# usbpropicprog-v2.net
KiCad netlist of a schematic drawn in EAGLE
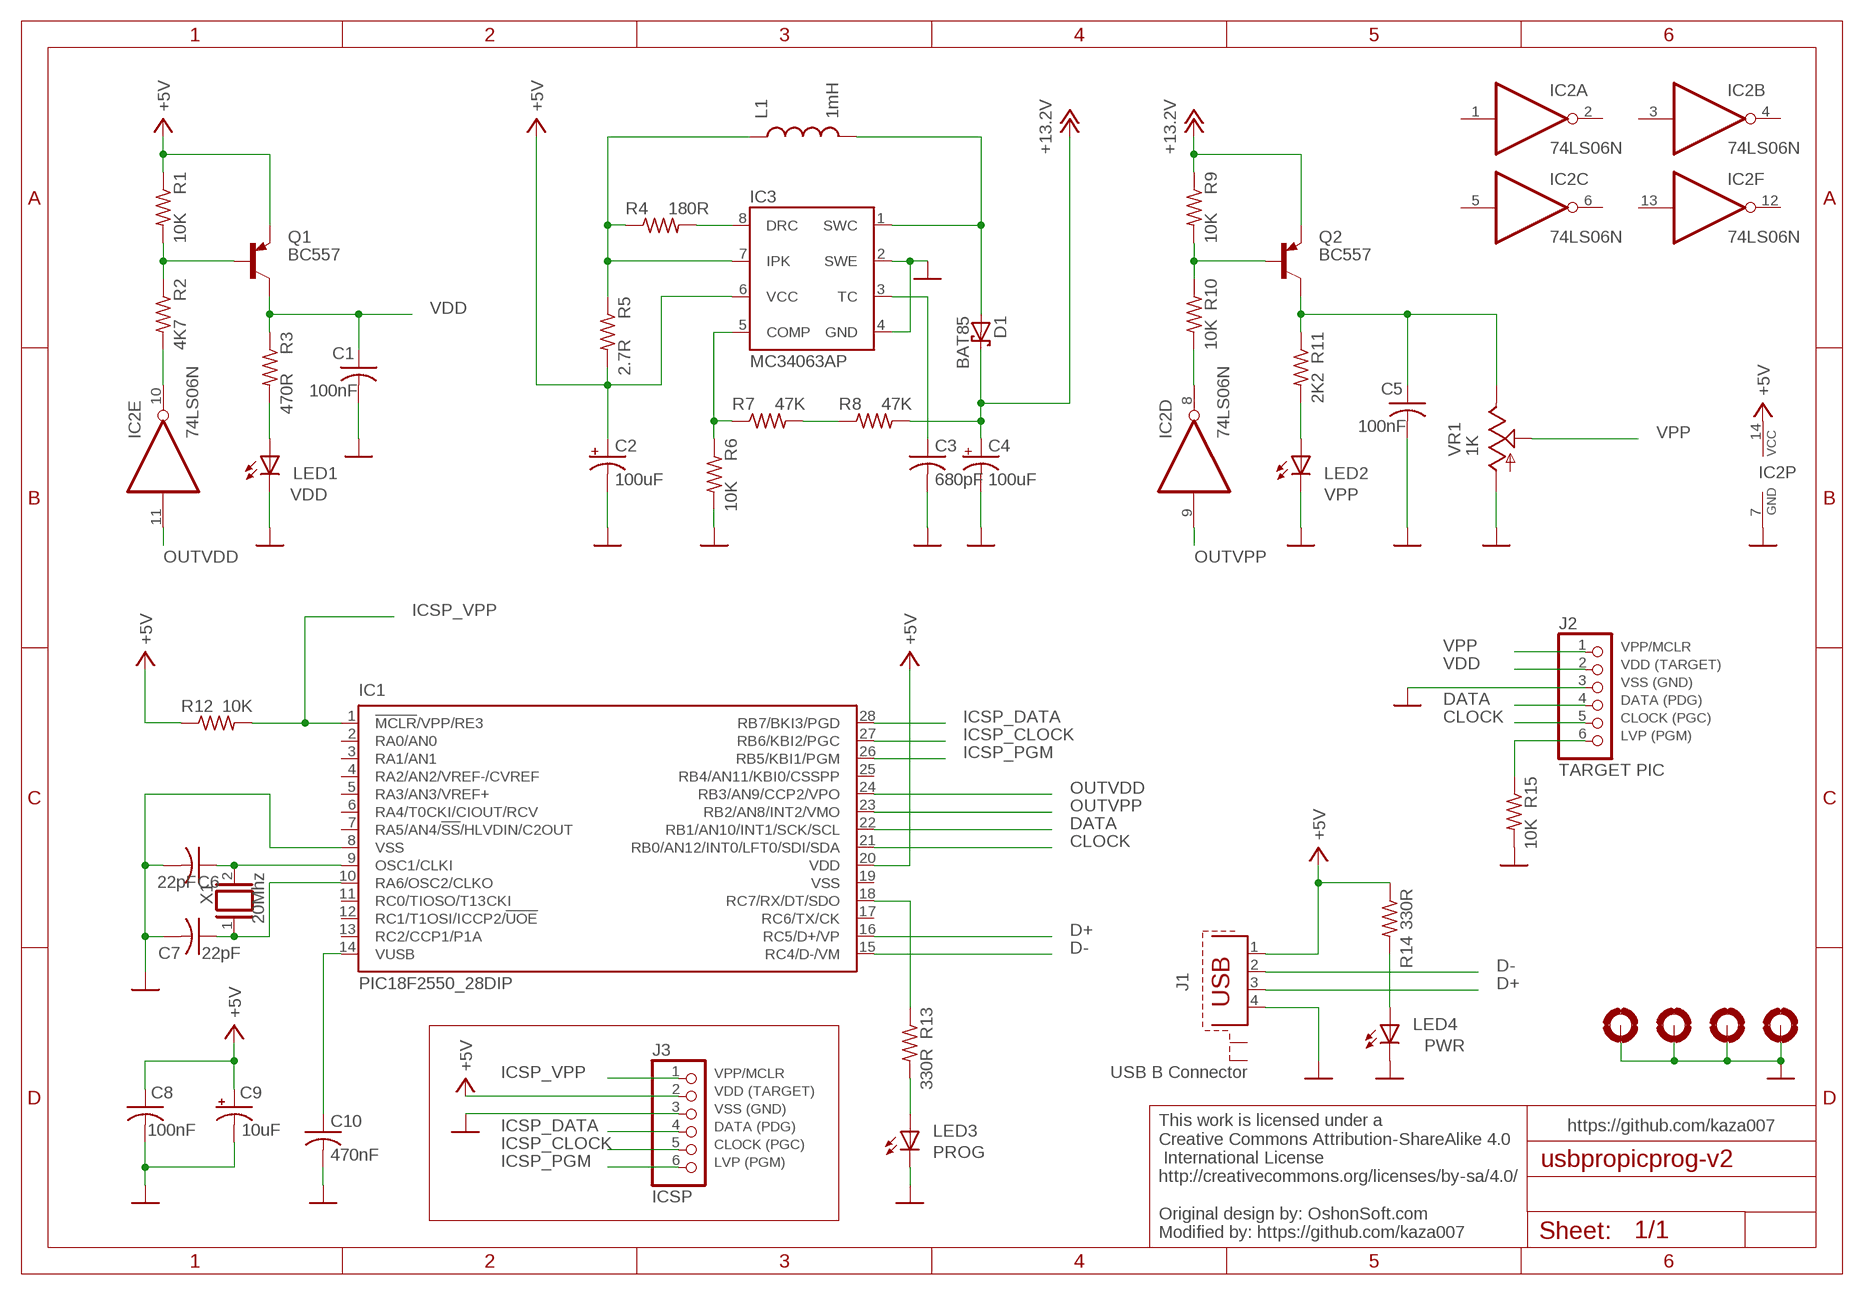
[diagram p0: schematic, sheet 1]

(export (version "E")
  (design (tool "Eeschema 10.0.6"))
  (components
    (comp (ref "C1")
      (value "100nF")
      (footprint "eagle-import:C050-025X075")
      (libsource (lib "eagle-import") (part "C-US050-025X075"))
    )
    (comp (ref "C2")
      (value "100uF")
      (footprint "eagle-import:E2,5-6,3")
      (libsource (lib "eagle-import") (part "POL-CAP-USE2,5-6,3"))
    )
    (comp (ref "C3")
      (value "680pF")
      (footprint "eagle-import:C050-025X075")
      (libsource (lib "eagle-import") (part "C-US050-025X075"))
    )
    (comp (ref "C4")
      (value "100uF")
      (footprint "eagle-import:E2,5-6,3")
      (libsource (lib "eagle-import") (part "POL-CAP-USE2,5-6,3"))
    )
    (comp (ref "C5")
      (value "100nF")
      (footprint "eagle-import:C050-025X075")
      (libsource (lib "eagle-import") (part "C-US050-025X075"))
    )
    (comp (ref "C6")
      (value "22pF")
      (footprint "eagle-import:C025-024X044")
      (libsource (lib "eagle-import") (part "C-US025-024X044"))
    )
    (comp (ref "C7")
      (value "22pF")
      (footprint "eagle-import:C025-024X044")
      (libsource (lib "eagle-import") (part "C-US025-024X044"))
    )
    (comp (ref "C8")
      (value "100nF")
      (footprint "eagle-import:C050-025X075")
      (libsource (lib "eagle-import") (part "C-US050-025X075"))
    )
    (comp (ref "C9")
      (value "10uF")
      (footprint "eagle-import:E2-5")
      (libsource (lib "eagle-import") (part "CPOL-USE2-5"))
    )
    (comp (ref "C10")
      (value "470nF")
      (footprint "eagle-import:C050-035X075")
      (libsource (lib "eagle-import") (part "C-US050-035X075"))
    )
    (comp (ref "D1")
      (value "BAT85")
      (footprint "eagle-import:DO41-7.6")
      (libsource (lib "eagle-import") (part "1N5819-T"))
    )
    (comp (ref "H1")
      (value "MOUNT-PAD-ROUND2.8")
      (footprint "eagle-import:2,8-PAD")
      (libsource (lib "eagle-import") (part "MOUNT-PAD-ROUND2.8"))
    )
    (comp (ref "H2")
      (value "MOUNT-PAD-ROUND2.8")
      (footprint "eagle-import:2,8-PAD")
      (libsource (lib "eagle-import") (part "MOUNT-PAD-ROUND2.8"))
    )
    (comp (ref "H3")
      (value "MOUNT-PAD-ROUND2.8")
      (footprint "eagle-import:2,8-PAD")
      (libsource (lib "eagle-import") (part "MOUNT-PAD-ROUND2.8"))
    )
    (comp (ref "H4")
      (value "MOUNT-PAD-ROUND2.8")
      (footprint "eagle-import:2,8-PAD")
      (libsource (lib "eagle-import") (part "MOUNT-PAD-ROUND2.8"))
    )
    (comp (ref "IC1")
      (value "PIC18F2550_28DIP")
      (footprint "eagle-import:DIL28-3")
      (fields (field (name "MF") "MICROCHIP") (field (name "MPN") "PIC18F2550-I/SP"))
      (libsource (lib "eagle-import") (part "PIC18F2_28DIP550"))
    )
    (comp (ref "IC2")
      (value "74LS06N")
      (footprint "eagle-import:DIL14")
      (libsource (lib "eagle-import") (part "7406NLS"))
    )
    (comp (ref "IC3")
      (value "MC34063AP")
      (footprint "eagle-import:DIL-08")
      (libsource (lib "eagle-import") (part "MC34063AP"))
    )
    (comp (ref "J1")
      (value "USB B Connector")
      (footprint "eagle-import:PN61729-S")
      (libsource (lib "eagle-import") (part "PN61729-S"))
    )
    (comp (ref "J2")
      (value "TARGET PIC")
      (footprint "eagle-import:1X06")
      (libsource (lib "eagle-import") (part "PINHD-1X6"))
    )
    (comp (ref "J3")
      (value "ICSP")
      (footprint "eagle-import:1X06")
      (libsource (lib "eagle-import") (part "PINHD-1X6"))
    )
    (comp (ref "L1")
      (value "1mH")
      (footprint "eagle-import:RLB0912")
      (libsource (lib "eagle-import") (part "INDUCTORRLB0912"))
    )
    (comp (ref "LED1")
      (value "VDD")
      (footprint "eagle-import:LED5MM")
      (libsource (lib "eagle-import") (part "LED5MM"))
    )
    (comp (ref "LED2")
      (value "VPP")
      (footprint "eagle-import:LED5MM")
      (libsource (lib "eagle-import") (part "LED5MM"))
    )
    (comp (ref "LED3")
      (value "PROG")
      (footprint "eagle-import:LED5MM")
      (libsource (lib "eagle-import") (part "LED5MM"))
    )
    (comp (ref "LED4")
      (value "PWR")
      (footprint "eagle-import:LED5MM")
      (libsource (lib "eagle-import") (part "LED5MM"))
    )
    (comp (ref "Q1")
      (value "BC557")
      (footprint "eagle-import:TO92-EBC")
      (libsource (lib "eagle-import") (part "BC557"))
    )
    (comp (ref "Q2")
      (value "BC557")
      (footprint "eagle-import:TO92-EBC")
      (libsource (lib "eagle-import") (part "BC557"))
    )
    (comp (ref "R1")
      (value "10K")
      (footprint "eagle-import:0207_10")
      (libsource (lib "eagle-import") (part "R-US_0207/10"))
    )
    (comp (ref "R2")
      (value "4K7")
      (footprint "eagle-import:0207_10")
      (libsource (lib "eagle-import") (part "R-US_0207/10"))
    )
    (comp (ref "R3")
      (value "470R")
      (footprint "eagle-import:0207_10")
      (libsource (lib "eagle-import") (part "R-US_0207/10"))
    )
    (comp (ref "R4")
      (value "180R")
      (footprint "eagle-import:0207_10")
      (libsource (lib "eagle-import") (part "R-US_0207/10"))
    )
    (comp (ref "R5")
      (value "2.7R")
      (footprint "eagle-import:0207_10")
      (libsource (lib "eagle-import") (part "R-US_0207/10"))
    )
    (comp (ref "R6")
      (value "10K")
      (footprint "eagle-import:0207_10")
      (libsource (lib "eagle-import") (part "R-US_0207/10"))
    )
    (comp (ref "R7")
      (value "47K")
      (footprint "eagle-import:0207_10")
      (libsource (lib "eagle-import") (part "R-US_0207/10"))
    )
    (comp (ref "R8")
      (value "47K")
      (footprint "eagle-import:0207_10")
      (libsource (lib "eagle-import") (part "R-US_0207/10"))
    )
    (comp (ref "R9")
      (value "10K")
      (footprint "eagle-import:0207_10")
      (libsource (lib "eagle-import") (part "R-US_0207/10"))
    )
    (comp (ref "R10")
      (value "10K")
      (footprint "eagle-import:0207_10")
      (libsource (lib "eagle-import") (part "R-US_0207/10"))
    )
    (comp (ref "R11")
      (value "2K2")
      (footprint "eagle-import:0207_10")
      (libsource (lib "eagle-import") (part "R-US_0207/10"))
    )
    (comp (ref "R12")
      (value "10K")
      (footprint "eagle-import:0207_10")
      (libsource (lib "eagle-import") (part "R-US_0207/10"))
    )
    (comp (ref "R13")
      (value "330R")
      (footprint "eagle-import:0207_10")
      (libsource (lib "eagle-import") (part "R-US_0207/10"))
    )
    (comp (ref "R14")
      (value "330R")
      (footprint "eagle-import:0207_10")
      (libsource (lib "eagle-import") (part "R-US_0207/10"))
    )
    (comp (ref "R15")
      (value "10K")
      (footprint "eagle-import:0207_10")
      (libsource (lib "eagle-import") (part "R-US_0207/10"))
    )
    (comp (ref "VR1")
      (value "1K")
      (footprint "eagle-import:R-TRIMMT93YA")
      (libsource (lib "eagle-import") (part "R-TRIMM_US"))
    )
    (comp (ref "X1")
      (value "20Mhz")
      (footprint "eagle-import:QS")
      (libsource (lib "eagle-import") (part "XTAL/S"))
    )
  )
  (nets
    (net (code "1") (name "+5V") (class "Default")
      (node (ref "C2") (pin "+") (pinfunction "+_+") (pintype "passive"))
      (node (ref "C8") (pin "1") (pinfunction "1_1") (pintype "passive"))
      (node (ref "C9") (pin "+") (pinfunction "+_+") (pintype "passive"))
      (node (ref "IC1") (pin "20") (pinfunction "VDD_20") (pintype "power_in"))
      (node (ref "IC2") (pin "14") (pinfunction "VCC_14") (pintype "power_in"))
      (node (ref "IC3") (pin "6") (pinfunction "VCC_6") (pintype "power_in"))
      (node (ref "J1") (pin "1") (pinfunction "1_1") (pintype "passive"))
      (node (ref "J3") (pin "2") (pinfunction "2_2") (pintype "passive"))
      (node (ref "Q1") (pin "E") (pinfunction "E_E") (pintype "passive"))
      (node (ref "R1") (pin "1") (pinfunction "1_1") (pintype "passive"))
      (node (ref "R12") (pin "1") (pinfunction "1_1") (pintype "passive"))
      (node (ref "R14") (pin "1") (pinfunction "1_1") (pintype "passive"))
      (node (ref "R5") (pin "2") (pinfunction "2_2") (pintype "passive"))
    )
    (net (code "2") (name "+13.2V") (class "Default")
      (node (ref "C4") (pin "+") (pinfunction "+_+") (pintype "passive"))
      (node (ref "D1") (pin "C") (pinfunction "C_C") (pintype "passive"))
      (node (ref "Q2") (pin "E") (pinfunction "E_E") (pintype "passive"))
      (node (ref "R8") (pin "2") (pinfunction "2_2") (pintype "passive"))
      (node (ref "R9") (pin "1") (pinfunction "1_1") (pintype "passive"))
    )
    (net (code "3") (name "/CLOCK") (class "Default")
      (node (ref "IC1") (pin "21") (pinfunction "RB0/AN12/INT0/LFT0/SDI/SDA_21") (pintype "bidirectional"))
      (node (ref "J2") (pin "5") (pinfunction "5_5") (pintype "passive"))
    )
    (net (code "4") (name "/D+") (class "Default")
      (node (ref "IC1") (pin "16") (pinfunction "RC5/D+/VP_16") (pintype "bidirectional"))
      (node (ref "J1") (pin "3") (pinfunction "3_3") (pintype "passive"))
    )
    (net (code "5") (name "/D-") (class "Default")
      (node (ref "IC1") (pin "15") (pinfunction "RC4/D-/VM_15") (pintype "bidirectional"))
      (node (ref "J1") (pin "2") (pinfunction "2_2") (pintype "passive"))
    )
    (net (code "6") (name "/DATA") (class "Default")
      (node (ref "IC1") (pin "22") (pinfunction "RB1/AN10/INT1/SCK/SCL_22") (pintype "bidirectional"))
      (node (ref "J2") (pin "4") (pinfunction "4_4") (pintype "passive"))
    )
    (net (code "7") (name "/ICSP_CLOCK") (class "Default")
      (node (ref "IC1") (pin "27") (pinfunction "RB6/KBI2/PGC_27") (pintype "bidirectional"))
      (node (ref "J3") (pin "5") (pinfunction "5_5") (pintype "passive"))
    )
    (net (code "8") (name "/ICSP_DATA") (class "Default")
      (node (ref "IC1") (pin "28") (pinfunction "RB7/BKI3/PGD_28") (pintype "bidirectional"))
      (node (ref "J3") (pin "4") (pinfunction "4_4") (pintype "passive"))
    )
    (net (code "9") (name "/ICSP_PGM") (class "Default")
      (node (ref "IC1") (pin "26") (pinfunction "RB5/KBI1/PGM_26") (pintype "bidirectional"))
      (node (ref "J3") (pin "6") (pinfunction "6_6") (pintype "passive"))
    )
    (net (code "10") (name "/ICSP_VPP") (class "Default")
      (node (ref "IC1") (pin "1") (pinfunction "~{MCLR}/VPP/RE3_1") (pintype "input"))
      (node (ref "J3") (pin "1") (pinfunction "1_1") (pintype "passive"))
      (node (ref "R12") (pin "2") (pinfunction "2_2") (pintype "passive"))
    )
    (net (code "11") (name "/OUTVDD") (class "Default")
      (node (ref "IC1") (pin "24") (pinfunction "RB3/AN9/CCP2/VPO_24") (pintype "bidirectional"))
      (node (ref "IC2") (pin "11") (pinfunction "I_11") (pintype "input"))
    )
    (net (code "12") (name "/OUTVPP") (class "Default")
      (node (ref "IC1") (pin "23") (pinfunction "RB2/AN8/INT2/VMO_23") (pintype "bidirectional"))
      (node (ref "IC2") (pin "9") (pinfunction "I_9") (pintype "input"))
    )
    (net (code "13") (name "/VDD") (class "Default")
      (node (ref "C1") (pin "1") (pinfunction "1_1") (pintype "passive"))
      (node (ref "J2") (pin "2") (pinfunction "2_2") (pintype "passive"))
      (node (ref "Q1") (pin "C") (pinfunction "C_C") (pintype "passive"))
      (node (ref "R3") (pin "1") (pinfunction "1_1") (pintype "passive"))
    )
    (net (code "14") (name "/VPP") (class "Default")
      (node (ref "J2") (pin "1") (pinfunction "1_1") (pintype "passive"))
      (node (ref "VR1") (pin "2") (pinfunction "S_2") (pintype "passive"))
    )
    (net (code "15") (name "/VSS") (class "Default")
      (node (ref "IC1") (pin "19") (pinfunction "VSS_19") (pintype "power_in"))
    )
    (net (code "16") (name "GND") (class "Default")
      (node (ref "C1") (pin "2") (pinfunction "2_2") (pintype "passive"))
      (node (ref "C10") (pin "2") (pinfunction "2_2") (pintype "passive"))
      (node (ref "C2") (pin "-") (pinfunction "-_-") (pintype "passive"))
      (node (ref "C3") (pin "2") (pinfunction "2_2") (pintype "passive"))
      (node (ref "C4") (pin "-") (pinfunction "-_-") (pintype "passive"))
      (node (ref "C5") (pin "2") (pinfunction "2_2") (pintype "passive"))
      (node (ref "C6") (pin "2") (pinfunction "2_2") (pintype "passive"))
      (node (ref "C7") (pin "2") (pinfunction "2_2") (pintype "passive"))
      (node (ref "C8") (pin "2") (pinfunction "2_2") (pintype "passive"))
      (node (ref "C9") (pin "-") (pinfunction "-_-") (pintype "passive"))
      (node (ref "H1") (pin "B2,8") (pinfunction "MOUNT_B2,8") (pintype "passive"))
      (node (ref "H2") (pin "B2,8") (pinfunction "MOUNT_B2,8") (pintype "passive"))
      (node (ref "H3") (pin "B2,8") (pinfunction "MOUNT_B2,8") (pintype "passive"))
      (node (ref "H4") (pin "B2,8") (pinfunction "MOUNT_B2,8") (pintype "passive"))
      (node (ref "IC1") (pin "8") (pinfunction "VSS_8") (pintype "power_in"))
      (node (ref "IC2") (pin "7") (pinfunction "GND_7") (pintype "power_in"))
      (node (ref "IC3") (pin "2") (pinfunction "SWE_2") (pintype "bidirectional"))
      (node (ref "IC3") (pin "4") (pinfunction "GND_4") (pintype "power_in"))
      (node (ref "J1") (pin "4") (pinfunction "4_4") (pintype "passive"))
      (node (ref "J2") (pin "3") (pinfunction "3_3") (pintype "passive"))
      (node (ref "J3") (pin "3") (pinfunction "3_3") (pintype "passive"))
      (node (ref "LED1") (pin "K") (pinfunction "C_K") (pintype "passive"))
      (node (ref "LED2") (pin "K") (pinfunction "C_K") (pintype "passive"))
      (node (ref "LED3") (pin "K") (pinfunction "C_K") (pintype "passive"))
      (node (ref "LED4") (pin "K") (pinfunction "C_K") (pintype "passive"))
      (node (ref "R15") (pin "2") (pinfunction "2_2") (pintype "passive"))
      (node (ref "R6") (pin "2") (pinfunction "2_2") (pintype "passive"))
      (node (ref "VR1") (pin "3") (pinfunction "A_3") (pintype "passive"))
    )
    (net (code "17") (name "Net-(IC1-OSC1{slash}CLKI)") (class "Default")
      (node (ref "C6") (pin "1") (pinfunction "1_1") (pintype "passive"))
      (node (ref "IC1") (pin "9") (pinfunction "OSC1/CLKI_9") (pintype "input"))
      (node (ref "X1") (pin "2") (pinfunction "2_2") (pintype "passive"))
    )
    (net (code "18") (name "Net-(IC1-RA6{slash}OSC2{slash}CLKO)") (class "Default")
      (node (ref "C7") (pin "1") (pinfunction "1_1") (pintype "passive"))
      (node (ref "IC1") (pin "10") (pinfunction "RA6/OSC2/CLKO_10") (pintype "output"))
      (node (ref "X1") (pin "1") (pinfunction "1_1") (pintype "passive"))
    )
    (net (code "19") (name "Net-(IC1-RC7{slash}RX{slash}DT{slash}SDO)") (class "Default")
      (node (ref "IC1") (pin "18") (pinfunction "RC7/RX/DT/SDO_18") (pintype "bidirectional"))
      (node (ref "R13") (pin "1") (pinfunction "1_1") (pintype "passive"))
    )
    (net (code "20") (name "Net-(IC1-VUSB)") (class "Default")
      (node (ref "C10") (pin "1") (pinfunction "1_1") (pintype "passive"))
      (node (ref "IC1") (pin "14") (pinfunction "VUSB_14") (pintype "bidirectional"))
    )
    (net (code "21") (name "Net-(IC2D-O)") (class "Default")
      (node (ref "IC2") (pin "8") (pinfunction "O_8") (pintype "open_collector"))
      (node (ref "R10") (pin "2") (pinfunction "2_2") (pintype "passive"))
    )
    (net (code "22") (name "Net-(IC2E-O)") (class "Default")
      (node (ref "IC2") (pin "10") (pinfunction "O_10") (pintype "open_collector"))
      (node (ref "R2") (pin "2") (pinfunction "2_2") (pintype "passive"))
    )
    (net (code "23") (name "Net-(IC3-COMP)") (class "Default")
      (node (ref "IC3") (pin "5") (pinfunction "COMP_5") (pintype "input"))
      (node (ref "R6") (pin "1") (pinfunction "1_1") (pintype "passive"))
      (node (ref "R7") (pin "1") (pinfunction "1_1") (pintype "passive"))
    )
    (net (code "24") (name "Net-(IC3-DRC)") (class "Default")
      (node (ref "IC3") (pin "8") (pinfunction "DRC_8") (pintype "input"))
      (node (ref "R4") (pin "2") (pinfunction "2_2") (pintype "passive"))
    )
    (net (code "25") (name "Net-(IC3-IPK)") (class "Default")
      (node (ref "IC3") (pin "7") (pinfunction "IPK_7") (pintype "input"))
      (node (ref "L1") (pin "1") (pinfunction "1_1") (pintype "passive"))
      (node (ref "R4") (pin "1") (pinfunction "1_1") (pintype "passive"))
      (node (ref "R5") (pin "1") (pinfunction "1_1") (pintype "passive"))
    )
    (net (code "26") (name "Net-(IC3-SWC)") (class "Default")
      (node (ref "D1") (pin "A") (pinfunction "A_A") (pintype "passive"))
      (node (ref "IC3") (pin "1") (pinfunction "SWC_1") (pintype "bidirectional"))
      (node (ref "L1") (pin "2") (pinfunction "2_2") (pintype "passive"))
    )
    (net (code "27") (name "Net-(IC3-TC)") (class "Default")
      (node (ref "C3") (pin "1") (pinfunction "1_1") (pintype "passive"))
      (node (ref "IC3") (pin "3") (pinfunction "TC_3") (pintype "passive"))
    )
    (net (code "28") (name "Net-(J2-Pad6)") (class "Default")
      (node (ref "J2") (pin "6") (pinfunction "6_6") (pintype "passive"))
      (node (ref "R15") (pin "1") (pinfunction "1_1") (pintype "passive"))
    )
    (net (code "29") (name "Net-(LED1-PadA)") (class "Default")
      (node (ref "LED1") (pin "A") (pinfunction "A_A") (pintype "passive"))
      (node (ref "R3") (pin "2") (pinfunction "2_2") (pintype "passive"))
    )
    (net (code "30") (name "Net-(LED2-PadA)") (class "Default")
      (node (ref "LED2") (pin "A") (pinfunction "A_A") (pintype "passive"))
      (node (ref "R11") (pin "2") (pinfunction "2_2") (pintype "passive"))
    )
    (net (code "31") (name "Net-(LED3-PadA)") (class "Default")
      (node (ref "LED3") (pin "A") (pinfunction "A_A") (pintype "passive"))
      (node (ref "R13") (pin "2") (pinfunction "2_2") (pintype "passive"))
    )
    (net (code "32") (name "Net-(LED4-PadA)") (class "Default")
      (node (ref "LED4") (pin "A") (pinfunction "A_A") (pintype "passive"))
      (node (ref "R14") (pin "2") (pinfunction "2_2") (pintype "passive"))
    )
    (net (code "33") (name "Net-(Q1-PadB)") (class "Default")
      (node (ref "Q1") (pin "B") (pinfunction "B_B") (pintype "passive"))
      (node (ref "R1") (pin "2") (pinfunction "2_2") (pintype "passive"))
      (node (ref "R2") (pin "1") (pinfunction "1_1") (pintype "passive"))
    )
    (net (code "34") (name "Net-(Q2-PadB)") (class "Default")
      (node (ref "Q2") (pin "B") (pinfunction "B_B") (pintype "passive"))
      (node (ref "R10") (pin "1") (pinfunction "1_1") (pintype "passive"))
      (node (ref "R9") (pin "2") (pinfunction "2_2") (pintype "passive"))
    )
    (net (code "35") (name "Net-(R7-Pad2)") (class "Default")
      (node (ref "R7") (pin "2") (pinfunction "2_2") (pintype "passive"))
      (node (ref "R8") (pin "1") (pinfunction "1_1") (pintype "passive"))
    )
    (net (code "36") (name "Net-(VR1-E)") (class "Default")
      (node (ref "C5") (pin "1") (pinfunction "1_1") (pintype "passive"))
      (node (ref "Q2") (pin "C") (pinfunction "C_C") (pintype "passive"))
      (node (ref "R11") (pin "1") (pinfunction "1_1") (pintype "passive"))
      (node (ref "VR1") (pin "1") (pinfunction "E_1") (pintype "passive"))
    )
    (net (code "37") (name "unconnected-(IC1-RA0{slash}AN0-Pad2)") (class "Default")
      (node (ref "IC1") (pin "2") (pinfunction "RA0/AN0_2") (pintype "bidirectional"))
    )
    (net (code "38") (name "unconnected-(IC1-RA1{slash}AN1-Pad3)") (class "Default")
      (node (ref "IC1") (pin "3") (pinfunction "RA1/AN1_3") (pintype "bidirectional"))
    )
    (net (code "39") (name "unconnected-(IC1-RA2{slash}AN2{slash}VREF-{slash}CVREF-Pad4)") (class "Default")
      (node (ref "IC1") (pin "4") (pinfunction "RA2/AN2/VREF-/CVREF_4") (pintype "bidirectional"))
    )
    (net (code "40") (name "unconnected-(IC1-RA3{slash}AN3{slash}VREF+-Pad5)") (class "Default")
      (node (ref "IC1") (pin "5") (pinfunction "RA3/AN3/VREF+_5") (pintype "bidirectional"))
    )
    (net (code "41") (name "unconnected-(IC1-RA4{slash}T0CKI{slash}CIOUT{slash}RCV-Pad6)") (class "Default")
      (node (ref "IC1") (pin "6") (pinfunction "RA4/T0CKI/CIOUT/RCV_6") (pintype "bidirectional"))
    )
    (net (code "42") (name "unconnected-(IC1-RA5{slash}AN4{slash}~{SS}{slash}HLVDIN{slash}C2OUT-Pad7)") (class "Default")
      (node (ref "IC1") (pin "7") (pinfunction "RA5/AN4/~{SS}/HLVDIN/C2OUT_7") (pintype "bidirectional"))
    )
    (net (code "43") (name "unconnected-(IC1-RB4{slash}AN11{slash}KBI0{slash}CSSPP-Pad25)") (class "Default")
      (node (ref "IC1") (pin "25") (pinfunction "RB4/AN11/KBI0/CSSPP_25") (pintype "bidirectional"))
    )
    (net (code "44") (name "unconnected-(IC1-RC0{slash}TIOSO{slash}T13CKI-Pad11)") (class "Default")
      (node (ref "IC1") (pin "11") (pinfunction "RC0/TIOSO/T13CKI_11") (pintype "bidirectional"))
    )
    (net (code "45") (name "unconnected-(IC1-RC1{slash}T1OSI{slash}ICCP2{slash}~{UOE}-Pad12)") (class "Default")
      (node (ref "IC1") (pin "12") (pinfunction "RC1/T1OSI/ICCP2/~{UOE}_12") (pintype "bidirectional"))
    )
    (net (code "46") (name "unconnected-(IC1-RC2{slash}CCP1{slash}P1A-Pad13)") (class "Default")
      (node (ref "IC1") (pin "13") (pinfunction "RC2/CCP1/P1A_13") (pintype "bidirectional"))
    )
    (net (code "47") (name "unconnected-(IC1-RC6{slash}TX{slash}CK-Pad17)") (class "Default")
      (node (ref "IC1") (pin "17") (pinfunction "RC6/TX/CK_17") (pintype "bidirectional"))
    )
    (net (code "48") (name "unconnected-(IC2A-I-Pad1)") (class "Default")
      (node (ref "IC2") (pin "1") (pinfunction "I_1") (pintype "input"))
    )
    (net (code "49") (name "unconnected-(IC2A-O-Pad2)") (class "Default")
      (node (ref "IC2") (pin "2") (pinfunction "O_2") (pintype "open_collector"))
    )
    (net (code "50") (name "unconnected-(IC2B-I-Pad3)") (class "Default")
      (node (ref "IC2") (pin "3") (pinfunction "I_3") (pintype "input"))
    )
    (net (code "51") (name "unconnected-(IC2B-O-Pad4)") (class "Default")
      (node (ref "IC2") (pin "4") (pinfunction "O_4") (pintype "open_collector"))
    )
    (net (code "52") (name "unconnected-(IC2C-I-Pad5)") (class "Default")
      (node (ref "IC2") (pin "5") (pinfunction "I_5") (pintype "input"))
    )
    (net (code "53") (name "unconnected-(IC2C-O-Pad6)") (class "Default")
      (node (ref "IC2") (pin "6") (pinfunction "O_6") (pintype "open_collector"))
    )
    (net (code "54") (name "unconnected-(IC2F-I-Pad13)") (class "Default")
      (node (ref "IC2") (pin "13") (pinfunction "I_13") (pintype "input"))
    )
    (net (code "55") (name "unconnected-(IC2F-O-Pad12)") (class "Default")
      (node (ref "IC2") (pin "12") (pinfunction "O_12") (pintype "open_collector"))
    )
    (net (code "56") (name "unconnected-(J1-PadS1)") (class "Default")
      (node (ref "J1") (pin "S1") (pinfunction "S1_S1") (pintype "passive"))
    )
    (net (code "57") (name "unconnected-(J1-PadS2)") (class "Default")
      (node (ref "J1") (pin "S2") (pinfunction "S2_S2") (pintype "passive"))
    )
  )
)
